# DRS4-TOP.net
KiCad netlist of a schematic drawn in Altium Designer
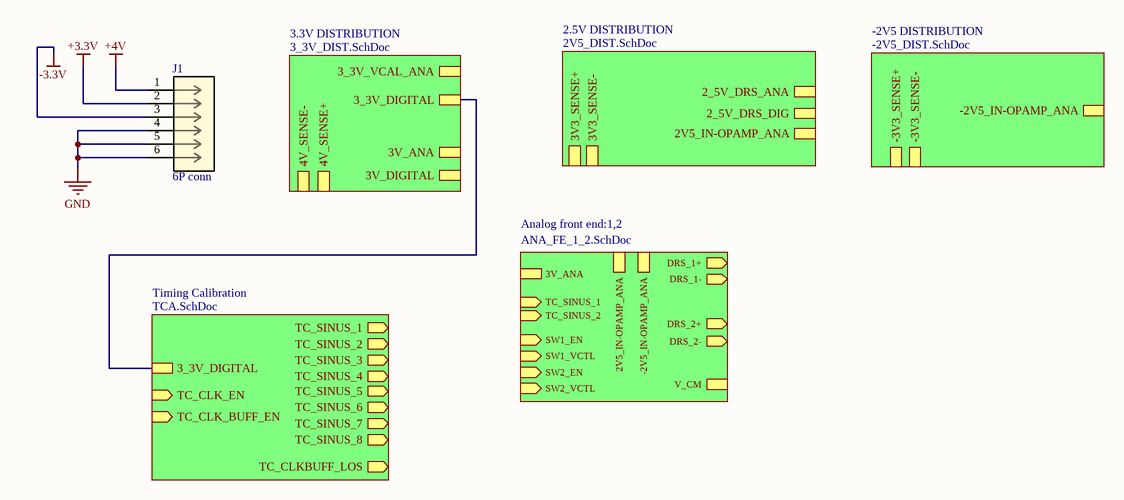
[diagram p0: DRS4-TOP.SchDoc]

(export (version "E")
  (design (tool "Eeschema 10.0.6"))
  (components
    (comp (ref "J1")
      (value "6P conn")
      (footprint "CONN_1586041-6_T")
      (description "Headers & Wire Housings RA HDR W/O PEGS 6P")
      (fields
        (field (name "MANUFACTURER_PART_NUMBER") "1586041-6")
        (field (name "COPYRIGHT") "Copyright (C) 2016 Accelerated Designs. All rights reserved")
      )
      (libsource (lib "1586041-6") (part "1586041-6"))
    )
  )
  (nets
    (net (code "1") (name "+3.3V") (class "Default")
      (node (ref "J1") (pin "2") (pinfunction "2_2") (pintype "passive"))
    )
    (net (code "2") (name "+4V") (class "Default")
      (node (ref "J1") (pin "1") (pinfunction "1_1") (pintype "passive"))
    )
    (net (code "3") (name "-3.3V") (class "Default")
      (node (ref "J1") (pin "3") (pinfunction "3_3") (pintype "passive"))
    )
    (net (code "43") (name "GND") (class "Default")
      (node (ref "J1") (pin "4") (pinfunction "4_4") (pintype "passive"))
      (node (ref "J1") (pin "5") (pinfunction "5_5") (pintype "passive"))
      (node (ref "J1") (pin "6") (pinfunction "6_6") (pintype "passive"))
    )
  )
)
